# Simple-Charger-LiIon-OpampBased-LM324-al.net
KiCad netlist of a schematic drawn in EAGLE
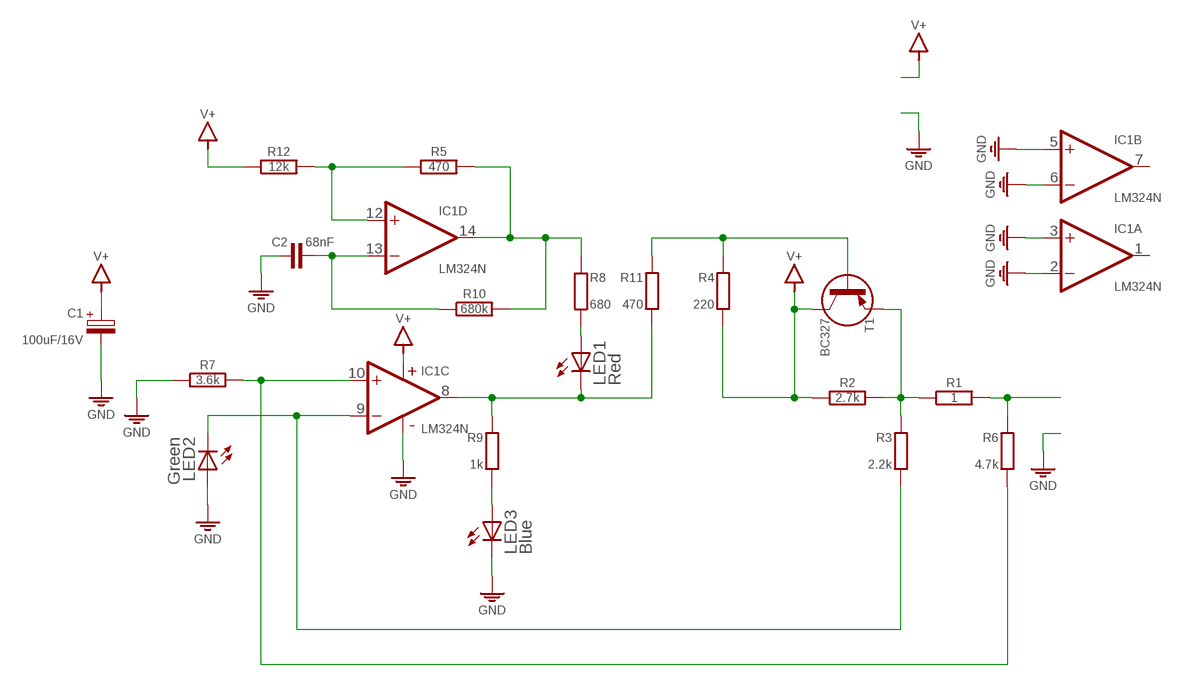
[diagram p0: schematic, sheet 1]

(export (version "E")
  (design (tool "Eeschema 10.0.6"))
  (components
    (comp (ref "C1")
      (value "100uF/16V")
      (footprint "eagle-import:E2,5-5")
      (libsource (lib "eagle-import") (part "CPOLE2.5-5"))
    )
    (comp (ref "C2")
      (value "68nF")
      (footprint "eagle-import:C050-020X044")
      (libsource (lib "eagle-import") (part "C-H050-020X044"))
    )
    (comp (ref "IC1")
      (value "LM324N")
      (footprint "eagle-import:DIL14")
      (libsource (lib "eagle-import") (part "LM324N"))
    )
    (comp (ref "LED1")
      (value "Red")
      (footprint "eagle-import:LED3MM")
      (libsource (lib "eagle-import") (part "LED3MM"))
    )
    (comp (ref "LED2")
      (value "Green")
      (footprint "eagle-import:LED3MM")
      (libsource (lib "eagle-import") (part "LED3MM"))
    )
    (comp (ref "LED3")
      (value "Blue")
      (footprint "eagle-import:LED3MM")
      (libsource (lib "eagle-import") (part "LED3MM"))
    )
    (comp (ref "R1")
      (value "1")
      (footprint "eagle-import:0204_10")
      (libsource (lib "eagle-import") (part "R-H0204/10"))
    )
    (comp (ref "R2")
      (value "2.7k")
      (footprint "eagle-import:0204_10-V")
      (libsource (lib "eagle-import") (part "R-H0204/10-V"))
    )
    (comp (ref "R3")
      (value "2.2k")
      (footprint "eagle-import:0204_10-V")
      (libsource (lib "eagle-import") (part "R0204/10-V"))
    )
    (comp (ref "R4")
      (value "220")
      (footprint "eagle-import:0204_10-V")
      (libsource (lib "eagle-import") (part "R0204/10-V"))
    )
    (comp (ref "R5")
      (value "470")
      (footprint "eagle-import:0204_7-V")
      (libsource (lib "eagle-import") (part "R-H0204/7-V"))
    )
    (comp (ref "R6")
      (value "4.7k")
      (footprint "eagle-import:0204_10-V")
      (libsource (lib "eagle-import") (part "R0204/10-V"))
    )
    (comp (ref "R7")
      (value "3.6k")
      (footprint "eagle-import:0204_10")
      (libsource (lib "eagle-import") (part "R-H0204/10"))
    )
    (comp (ref "R8")
      (value "680")
      (footprint "eagle-import:0204_10-V")
      (libsource (lib "eagle-import") (part "R0204/10-V"))
    )
    (comp (ref "R9")
      (value "1k")
      (footprint "eagle-import:0204_10")
      (libsource (lib "eagle-import") (part "R0204/10"))
    )
    (comp (ref "R10")
      (value "680k")
      (footprint "eagle-import:0204_10-V")
      (libsource (lib "eagle-import") (part "R-H0204/10-V"))
    )
    (comp (ref "R11")
      (value "470")
      (footprint "eagle-import:0204_10-V")
      (libsource (lib "eagle-import") (part "R0204/10-V"))
    )
    (comp (ref "R12")
      (value "12k")
      (footprint "eagle-import:0204_10-V")
      (libsource (lib "eagle-import") (part "R-H0204/10-V"))
    )
    (comp (ref "T1")
      (value "BC327")
      (footprint "eagle-import:TO92")
      (libsource (lib "eagle-import") (part "BC327"))
    )
  )
  (nets
    (net (code "1") (name "GND") (class "Default")
      (node (ref "C1") (pin "-") (pinfunction "-_-") (pintype "passive"))
      (node (ref "C2") (pin "1") (pinfunction "1_1") (pintype "passive"))
      (node (ref "IC1") (pin "11") (pinfunction "V-_11") (pintype "power_in"))
      (node (ref "IC1") (pin "2") (pinfunction "-IN_2") (pintype "input"))
      (node (ref "IC1") (pin "3") (pinfunction "+IN_3") (pintype "input"))
      (node (ref "IC1") (pin "5") (pinfunction "+IN_5") (pintype "input"))
      (node (ref "IC1") (pin "6") (pinfunction "-IN_6") (pintype "input"))
      (node (ref "LED2") (pin "A") (pinfunction "A_A") (pintype "passive"))
      (node (ref "LED3") (pin "K") (pinfunction "C_K") (pintype "passive"))
      (node (ref "R7") (pin "1") (pinfunction "1_1") (pintype "passive"))
    )
    (net (code "2") (name "Net-(IC1C-+IN)") (class "Default")
      (node (ref "IC1") (pin "10") (pinfunction "+IN_10") (pintype "input"))
      (node (ref "R6") (pin "2") (pinfunction "2_2") (pintype "passive"))
      (node (ref "R7") (pin "2") (pinfunction "2_2") (pintype "passive"))
    )
    (net (code "3") (name "Net-(IC1C--IN)") (class "Default")
      (node (ref "IC1") (pin "9") (pinfunction "-IN_9") (pintype "input"))
      (node (ref "LED2") (pin "K") (pinfunction "C_K") (pintype "passive"))
      (node (ref "R3") (pin "2") (pinfunction "2_2") (pintype "passive"))
    )
    (net (code "4") (name "Net-(IC1C-OUT)") (class "Default")
      (node (ref "IC1") (pin "8") (pinfunction "OUT_8") (pintype "output"))
      (node (ref "LED1") (pin "K") (pinfunction "C_K") (pintype "passive"))
      (node (ref "R11") (pin "2") (pinfunction "2_2") (pintype "passive"))
      (node (ref "R9") (pin "1") (pinfunction "1_1") (pintype "passive"))
    )
    (net (code "5") (name "Net-(IC1D-+IN)") (class "Default")
      (node (ref "IC1") (pin "12") (pinfunction "+IN_12") (pintype "input"))
      (node (ref "R12") (pin "2") (pinfunction "2_2") (pintype "passive"))
      (node (ref "R5") (pin "1") (pinfunction "1_1") (pintype "passive"))
    )
    (net (code "6") (name "Net-(IC1D--IN)") (class "Default")
      (node (ref "C2") (pin "2") (pinfunction "2_2") (pintype "passive"))
      (node (ref "IC1") (pin "13") (pinfunction "-IN_13") (pintype "input"))
      (node (ref "R10") (pin "1") (pinfunction "1_1") (pintype "passive"))
    )
    (net (code "7") (name "Net-(IC1D-OUT)") (class "Default")
      (node (ref "IC1") (pin "14") (pinfunction "OUT_14") (pintype "output"))
      (node (ref "R10") (pin "2") (pinfunction "2_2") (pintype "passive"))
      (node (ref "R5") (pin "2") (pinfunction "2_2") (pintype "passive"))
      (node (ref "R8") (pin "1") (pinfunction "1_1") (pintype "passive"))
    )
    (net (code "8") (name "Net-(LED1-PadA)") (class "Default")
      (node (ref "LED1") (pin "A") (pinfunction "A_A") (pintype "passive"))
      (node (ref "R8") (pin "2") (pinfunction "2_2") (pintype "passive"))
    )
    (net (code "9") (name "Net-(LED3-PadA)") (class "Default")
      (node (ref "LED3") (pin "A") (pinfunction "A_A") (pintype "passive"))
      (node (ref "R9") (pin "2") (pinfunction "2_2") (pintype "passive"))
    )
    (net (code "10") (name "Net-(R1-Pad2)") (class "Default")
      (node (ref "R1") (pin "2") (pinfunction "2_2") (pintype "passive"))
      (node (ref "R6") (pin "1") (pinfunction "1_1") (pintype "passive"))
    )
    (net (code "11") (name "Net-(T1-B)") (class "Default")
      (node (ref "R11") (pin "1") (pinfunction "1_1") (pintype "passive"))
      (node (ref "R4") (pin "1") (pinfunction "1_1") (pintype "passive"))
      (node (ref "T1") (pin "2") (pinfunction "B_2") (pintype "passive"))
    )
    (net (code "12") (name "Net-(T1-E)") (class "Default")
      (node (ref "R1") (pin "1") (pinfunction "1_1") (pintype "passive"))
      (node (ref "R2") (pin "2") (pinfunction "2_2") (pintype "passive"))
      (node (ref "R3") (pin "1") (pinfunction "1_1") (pintype "passive"))
      (node (ref "T1") (pin "3") (pinfunction "E_3") (pintype "passive"))
    )
    (net (code "13") (name "V+") (class "Default")
      (node (ref "C1") (pin "+") (pinfunction "+_+") (pintype "passive"))
      (node (ref "IC1") (pin "4") (pinfunction "V+_4") (pintype "power_in"))
      (node (ref "R12") (pin "1") (pinfunction "1_1") (pintype "passive"))
      (node (ref "R2") (pin "1") (pinfunction "1_1") (pintype "passive"))
      (node (ref "R4") (pin "2") (pinfunction "2_2") (pintype "passive"))
      (node (ref "T1") (pin "1") (pinfunction "C_1") (pintype "passive"))
    )
    (net (code "14") (name "unconnected-(IC1A-OUT-Pad1)") (class "Default")
      (node (ref "IC1") (pin "1") (pinfunction "OUT_1") (pintype "output"))
    )
    (net (code "15") (name "unconnected-(IC1B-OUT-Pad7)") (class "Default")
      (node (ref "IC1") (pin "7") (pinfunction "OUT_7") (pintype "output"))
    )
  )
)
